# Adafruit_DotStar_2020_8x8_Matrix.net
KiCad netlist of a schematic drawn in EAGLE
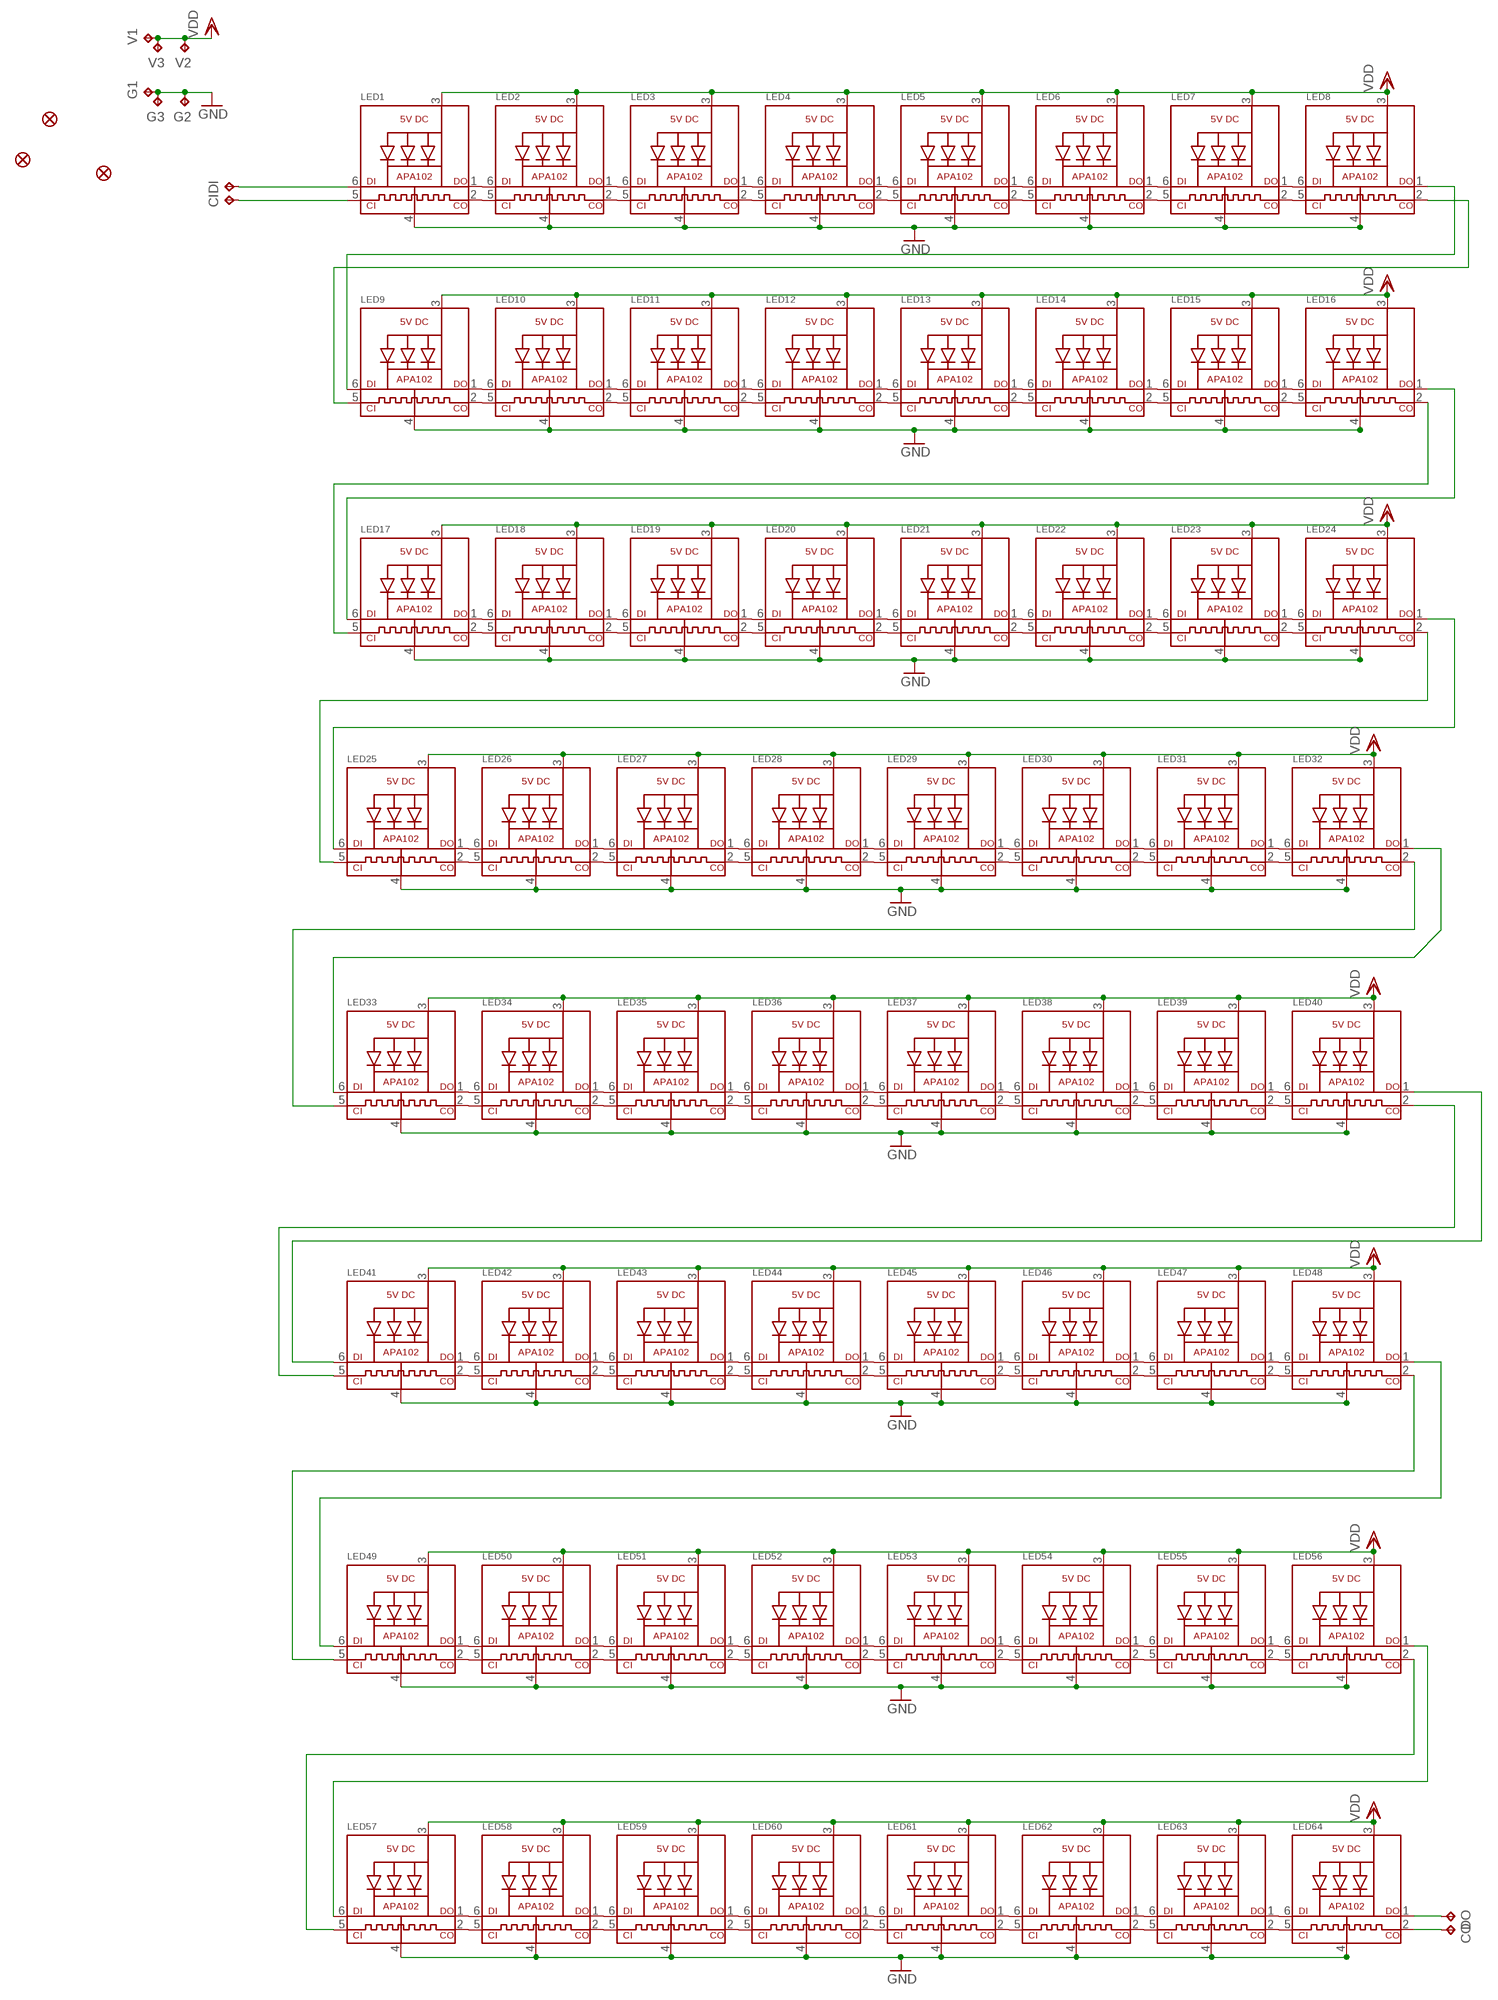
[diagram p0: schematic, sheet 1]

(export (version "E")
  (design (tool "Eeschema 10.0.6"))
  (components
    (comp (ref "CI")
      (value "TPTP20R")
      (footprint "eagle-import:TP20R")
      (libsource (lib "eagle-import") (part "TPTP20R"))
    )
    (comp (ref "CO")
      (value "TPTP20R")
      (footprint "eagle-import:TP20R")
      (libsource (lib "eagle-import") (part "TPTP20R"))
    )
    (comp (ref "DI")
      (value "TPTP20R")
      (footprint "eagle-import:TP20R")
      (libsource (lib "eagle-import") (part "TPTP20R"))
    )
    (comp (ref "DO")
      (value "TPTP20R")
      (footprint "eagle-import:TP20R")
      (libsource (lib "eagle-import") (part "TPTP20R"))
    )
    (comp (ref "FID1")
      (value "FIDUCIAL_0.5MM")
      (footprint "eagle-import:FIDUCIAL_0.5MM")
      (libsource (lib "eagle-import") (part "FIDUCIAL_0.5MM"))
    )
    (comp (ref "FID2")
      (value "FIDUCIAL_0.5MM")
      (footprint "eagle-import:FIDUCIAL_0.5MM")
      (libsource (lib "eagle-import") (part "FIDUCIAL_0.5MM"))
    )
    (comp (ref "FID3")
      (value "FIDUCIAL_0.5MM")
      (footprint "eagle-import:FIDUCIAL_0.5MM")
      (libsource (lib "eagle-import") (part "FIDUCIAL_0.5MM"))
    )
    (comp (ref "G1")
      (value "TPTP20R")
      (footprint "eagle-import:TP20R")
      (libsource (lib "eagle-import") (part "TPTP20R"))
    )
    (comp (ref "G2")
      (value "TPTP20R")
      (footprint "eagle-import:TP20R")
      (libsource (lib "eagle-import") (part "TPTP20R"))
    )
    (comp (ref "G3")
      (value "TPTP20R")
      (footprint "eagle-import:TP20R")
      (libsource (lib "eagle-import") (part "TPTP20R"))
    )
    (comp (ref "LED1")
      (value "APA1022020")
      (footprint "eagle-import:APA102_2020")
      (libsource (lib "eagle-import") (part "APA1022020"))
    )
    (comp (ref "LED2")
      (value "APA1022020")
      (footprint "eagle-import:APA102_2020")
      (libsource (lib "eagle-import") (part "APA1022020"))
    )
    (comp (ref "LED3")
      (value "APA1022020")
      (footprint "eagle-import:APA102_2020")
      (libsource (lib "eagle-import") (part "APA1022020"))
    )
    (comp (ref "LED4")
      (value "APA1022020")
      (footprint "eagle-import:APA102_2020")
      (libsource (lib "eagle-import") (part "APA1022020"))
    )
    (comp (ref "LED5")
      (value "APA1022020")
      (footprint "eagle-import:APA102_2020")
      (libsource (lib "eagle-import") (part "APA1022020"))
    )
    (comp (ref "LED6")
      (value "APA1022020")
      (footprint "eagle-import:APA102_2020")
      (libsource (lib "eagle-import") (part "APA1022020"))
    )
    (comp (ref "LED7")
      (value "APA1022020")
      (footprint "eagle-import:APA102_2020")
      (libsource (lib "eagle-import") (part "APA1022020"))
    )
    (comp (ref "LED8")
      (value "APA1022020")
      (footprint "eagle-import:APA102_2020")
      (libsource (lib "eagle-import") (part "APA1022020"))
    )
    (comp (ref "LED9")
      (value "APA1022020")
      (footprint "eagle-import:APA102_2020")
      (libsource (lib "eagle-import") (part "APA1022020"))
    )
    (comp (ref "LED10")
      (value "APA1022020")
      (footprint "eagle-import:APA102_2020")
      (libsource (lib "eagle-import") (part "APA1022020"))
    )
    (comp (ref "LED11")
      (value "APA1022020")
      (footprint "eagle-import:APA102_2020")
      (libsource (lib "eagle-import") (part "APA1022020"))
    )
    (comp (ref "LED12")
      (value "APA1022020")
      (footprint "eagle-import:APA102_2020")
      (libsource (lib "eagle-import") (part "APA1022020"))
    )
    (comp (ref "LED13")
      (value "APA1022020")
      (footprint "eagle-import:APA102_2020")
      (libsource (lib "eagle-import") (part "APA1022020"))
    )
    (comp (ref "LED14")
      (value "APA1022020")
      (footprint "eagle-import:APA102_2020")
      (libsource (lib "eagle-import") (part "APA1022020"))
    )
    (comp (ref "LED15")
      (value "APA1022020")
      (footprint "eagle-import:APA102_2020")
      (libsource (lib "eagle-import") (part "APA1022020"))
    )
    (comp (ref "LED16")
      (value "APA1022020")
      (footprint "eagle-import:APA102_2020")
      (libsource (lib "eagle-import") (part "APA1022020"))
    )
    (comp (ref "LED17")
      (value "APA1022020")
      (footprint "eagle-import:APA102_2020")
      (libsource (lib "eagle-import") (part "APA1022020"))
    )
    (comp (ref "LED18")
      (value "APA1022020")
      (footprint "eagle-import:APA102_2020")
      (libsource (lib "eagle-import") (part "APA1022020"))
    )
    (comp (ref "LED19")
      (value "APA1022020")
      (footprint "eagle-import:APA102_2020")
      (libsource (lib "eagle-import") (part "APA1022020"))
    )
    (comp (ref "LED20")
      (value "APA1022020")
      (footprint "eagle-import:APA102_2020")
      (libsource (lib "eagle-import") (part "APA1022020"))
    )
    (comp (ref "LED21")
      (value "APA1022020")
      (footprint "eagle-import:APA102_2020")
      (libsource (lib "eagle-import") (part "APA1022020"))
    )
    (comp (ref "LED22")
      (value "APA1022020")
      (footprint "eagle-import:APA102_2020")
      (libsource (lib "eagle-import") (part "APA1022020"))
    )
    (comp (ref "LED23")
      (value "APA1022020")
      (footprint "eagle-import:APA102_2020")
      (libsource (lib "eagle-import") (part "APA1022020"))
    )
    (comp (ref "LED24")
      (value "APA1022020")
      (footprint "eagle-import:APA102_2020")
      (libsource (lib "eagle-import") (part "APA1022020"))
    )
    (comp (ref "LED25")
      (value "APA1022020")
      (footprint "eagle-import:APA102_2020")
      (libsource (lib "eagle-import") (part "APA1022020"))
    )
    (comp (ref "LED26")
      (value "APA1022020")
      (footprint "eagle-import:APA102_2020")
      (libsource (lib "eagle-import") (part "APA1022020"))
    )
    (comp (ref "LED27")
      (value "APA1022020")
      (footprint "eagle-import:APA102_2020")
      (libsource (lib "eagle-import") (part "APA1022020"))
    )
    (comp (ref "LED28")
      (value "APA1022020")
      (footprint "eagle-import:APA102_2020")
      (libsource (lib "eagle-import") (part "APA1022020"))
    )
    (comp (ref "LED29")
      (value "APA1022020")
      (footprint "eagle-import:APA102_2020")
      (libsource (lib "eagle-import") (part "APA1022020"))
    )
    (comp (ref "LED30")
      (value "APA1022020")
      (footprint "eagle-import:APA102_2020")
      (libsource (lib "eagle-import") (part "APA1022020"))
    )
    (comp (ref "LED31")
      (value "APA1022020")
      (footprint "eagle-import:APA102_2020")
      (libsource (lib "eagle-import") (part "APA1022020"))
    )
    (comp (ref "LED32")
      (value "APA1022020")
      (footprint "eagle-import:APA102_2020")
      (libsource (lib "eagle-import") (part "APA1022020"))
    )
    (comp (ref "LED33")
      (value "APA1022020")
      (footprint "eagle-import:APA102_2020")
      (libsource (lib "eagle-import") (part "APA1022020"))
    )
    (comp (ref "LED34")
      (value "APA1022020")
      (footprint "eagle-import:APA102_2020")
      (libsource (lib "eagle-import") (part "APA1022020"))
    )
    (comp (ref "LED35")
      (value "APA1022020")
      (footprint "eagle-import:APA102_2020")
      (libsource (lib "eagle-import") (part "APA1022020"))
    )
    (comp (ref "LED36")
      (value "APA1022020")
      (footprint "eagle-import:APA102_2020")
      (libsource (lib "eagle-import") (part "APA1022020"))
    )
    (comp (ref "LED37")
      (value "APA1022020")
      (footprint "eagle-import:APA102_2020")
      (libsource (lib "eagle-import") (part "APA1022020"))
    )
    (comp (ref "LED38")
      (value "APA1022020")
      (footprint "eagle-import:APA102_2020")
      (libsource (lib "eagle-import") (part "APA1022020"))
    )
    (comp (ref "LED39")
      (value "APA1022020")
      (footprint "eagle-import:APA102_2020")
      (libsource (lib "eagle-import") (part "APA1022020"))
    )
    (comp (ref "LED40")
      (value "APA1022020")
      (footprint "eagle-import:APA102_2020")
      (libsource (lib "eagle-import") (part "APA1022020"))
    )
    (comp (ref "LED41")
      (value "APA1022020")
      (footprint "eagle-import:APA102_2020")
      (libsource (lib "eagle-import") (part "APA1022020"))
    )
    (comp (ref "LED42")
      (value "APA1022020")
      (footprint "eagle-import:APA102_2020")
      (libsource (lib "eagle-import") (part "APA1022020"))
    )
    (comp (ref "LED43")
      (value "APA1022020")
      (footprint "eagle-import:APA102_2020")
      (libsource (lib "eagle-import") (part "APA1022020"))
    )
    (comp (ref "LED44")
      (value "APA1022020")
      (footprint "eagle-import:APA102_2020")
      (libsource (lib "eagle-import") (part "APA1022020"))
    )
    (comp (ref "LED45")
      (value "APA1022020")
      (footprint "eagle-import:APA102_2020")
      (libsource (lib "eagle-import") (part "APA1022020"))
    )
    (comp (ref "LED46")
      (value "APA1022020")
      (footprint "eagle-import:APA102_2020")
      (libsource (lib "eagle-import") (part "APA1022020"))
    )
    (comp (ref "LED47")
      (value "APA1022020")
      (footprint "eagle-import:APA102_2020")
      (libsource (lib "eagle-import") (part "APA1022020"))
    )
    (comp (ref "LED48")
      (value "APA1022020")
      (footprint "eagle-import:APA102_2020")
      (libsource (lib "eagle-import") (part "APA1022020"))
    )
    (comp (ref "LED49")
      (value "APA1022020")
      (footprint "eagle-import:APA102_2020")
      (libsource (lib "eagle-import") (part "APA1022020"))
    )
    (comp (ref "LED50")
      (value "APA1022020")
      (footprint "eagle-import:APA102_2020")
      (libsource (lib "eagle-import") (part "APA1022020"))
    )
    (comp (ref "LED51")
      (value "APA1022020")
      (footprint "eagle-import:APA102_2020")
      (libsource (lib "eagle-import") (part "APA1022020"))
    )
    (comp (ref "LED52")
      (value "APA1022020")
      (footprint "eagle-import:APA102_2020")
      (libsource (lib "eagle-import") (part "APA1022020"))
    )
    (comp (ref "LED53")
      (value "APA1022020")
      (footprint "eagle-import:APA102_2020")
      (libsource (lib "eagle-import") (part "APA1022020"))
    )
    (comp (ref "LED54")
      (value "APA1022020")
      (footprint "eagle-import:APA102_2020")
      (libsource (lib "eagle-import") (part "APA1022020"))
    )
    (comp (ref "LED55")
      (value "APA1022020")
      (footprint "eagle-import:APA102_2020")
      (libsource (lib "eagle-import") (part "APA1022020"))
    )
    (comp (ref "LED56")
      (value "APA1022020")
      (footprint "eagle-import:APA102_2020")
      (libsource (lib "eagle-import") (part "APA1022020"))
    )
    (comp (ref "LED57")
      (value "APA1022020")
      (footprint "eagle-import:APA102_2020")
      (libsource (lib "eagle-import") (part "APA1022020"))
    )
    (comp (ref "LED58")
      (value "APA1022020")
      (footprint "eagle-import:APA102_2020")
      (libsource (lib "eagle-import") (part "APA1022020"))
    )
    (comp (ref "LED59")
      (value "APA1022020")
      (footprint "eagle-import:APA102_2020")
      (libsource (lib "eagle-import") (part "APA1022020"))
    )
    (comp (ref "LED60")
      (value "APA1022020")
      (footprint "eagle-import:APA102_2020")
      (libsource (lib "eagle-import") (part "APA1022020"))
    )
    (comp (ref "LED61")
      (value "APA1022020")
      (footprint "eagle-import:APA102_2020")
      (libsource (lib "eagle-import") (part "APA1022020"))
    )
    (comp (ref "LED62")
      (value "APA1022020")
      (footprint "eagle-import:APA102_2020")
      (libsource (lib "eagle-import") (part "APA1022020"))
    )
    (comp (ref "LED63")
      (value "APA1022020")
      (footprint "eagle-import:APA102_2020")
      (libsource (lib "eagle-import") (part "APA1022020"))
    )
    (comp (ref "LED64")
      (value "APA1022020")
      (footprint "eagle-import:APA102_2020")
      (libsource (lib "eagle-import") (part "APA1022020"))
    )
    (comp (ref "V1")
      (value "TPTP20R")
      (footprint "eagle-import:TP20R")
      (libsource (lib "eagle-import") (part "TPTP20R"))
    )
    (comp (ref "V2")
      (value "TPTP20R")
      (footprint "eagle-import:TP20R")
      (libsource (lib "eagle-import") (part "TPTP20R"))
    )
    (comp (ref "V3")
      (value "TPTP20R")
      (footprint "eagle-import:TP20R")
      (libsource (lib "eagle-import") (part "TPTP20R"))
    )
  )
  (nets
    (net (code "1") (name "GND") (class "Default")
      (node (ref "G1") (pin "TP") (pinfunction "TP_TP") (pintype "input"))
      (node (ref "G2") (pin "TP") (pinfunction "TP_TP") (pintype "input"))
      (node (ref "G3") (pin "TP") (pinfunction "TP_TP") (pintype "input"))
      (node (ref "LED1") (pin "4") (pinfunction "GND_4") (pintype "power_in"))
      (node (ref "LED10") (pin "4") (pinfunction "GND_4") (pintype "power_in"))
      (node (ref "LED11") (pin "4") (pinfunction "GND_4") (pintype "power_in"))
      (node (ref "LED12") (pin "4") (pinfunction "GND_4") (pintype "power_in"))
      (node (ref "LED13") (pin "4") (pinfunction "GND_4") (pintype "power_in"))
      (node (ref "LED14") (pin "4") (pinfunction "GND_4") (pintype "power_in"))
      (node (ref "LED15") (pin "4") (pinfunction "GND_4") (pintype "power_in"))
      (node (ref "LED16") (pin "4") (pinfunction "GND_4") (pintype "power_in"))
      (node (ref "LED17") (pin "4") (pinfunction "GND_4") (pintype "power_in"))
      (node (ref "LED18") (pin "4") (pinfunction "GND_4") (pintype "power_in"))
      (node (ref "LED19") (pin "4") (pinfunction "GND_4") (pintype "power_in"))
      (node (ref "LED2") (pin "4") (pinfunction "GND_4") (pintype "power_in"))
      (node (ref "LED20") (pin "4") (pinfunction "GND_4") (pintype "power_in"))
      (node (ref "LED21") (pin "4") (pinfunction "GND_4") (pintype "power_in"))
      (node (ref "LED22") (pin "4") (pinfunction "GND_4") (pintype "power_in"))
      (node (ref "LED23") (pin "4") (pinfunction "GND_4") (pintype "power_in"))
      (node (ref "LED24") (pin "4") (pinfunction "GND_4") (pintype "power_in"))
      (node (ref "LED25") (pin "4") (pinfunction "GND_4") (pintype "power_in"))
      (node (ref "LED26") (pin "4") (pinfunction "GND_4") (pintype "power_in"))
      (node (ref "LED27") (pin "4") (pinfunction "GND_4") (pintype "power_in"))
      (node (ref "LED28") (pin "4") (pinfunction "GND_4") (pintype "power_in"))
      (node (ref "LED29") (pin "4") (pinfunction "GND_4") (pintype "power_in"))
      (node (ref "LED3") (pin "4") (pinfunction "GND_4") (pintype "power_in"))
      (node (ref "LED30") (pin "4") (pinfunction "GND_4") (pintype "power_in"))
      (node (ref "LED31") (pin "4") (pinfunction "GND_4") (pintype "power_in"))
      (node (ref "LED32") (pin "4") (pinfunction "GND_4") (pintype "power_in"))
      (node (ref "LED33") (pin "4") (pinfunction "GND_4") (pintype "power_in"))
      (node (ref "LED34") (pin "4") (pinfunction "GND_4") (pintype "power_in"))
      (node (ref "LED35") (pin "4") (pinfunction "GND_4") (pintype "power_in"))
      (node (ref "LED36") (pin "4") (pinfunction "GND_4") (pintype "power_in"))
      (node (ref "LED37") (pin "4") (pinfunction "GND_4") (pintype "power_in"))
      (node (ref "LED38") (pin "4") (pinfunction "GND_4") (pintype "power_in"))
      (node (ref "LED39") (pin "4") (pinfunction "GND_4") (pintype "power_in"))
      (node (ref "LED4") (pin "4") (pinfunction "GND_4") (pintype "power_in"))
      (node (ref "LED40") (pin "4") (pinfunction "GND_4") (pintype "power_in"))
      (node (ref "LED41") (pin "4") (pinfunction "GND_4") (pintype "power_in"))
      (node (ref "LED42") (pin "4") (pinfunction "GND_4") (pintype "power_in"))
      (node (ref "LED43") (pin "4") (pinfunction "GND_4") (pintype "power_in"))
      (node (ref "LED44") (pin "4") (pinfunction "GND_4") (pintype "power_in"))
      (node (ref "LED45") (pin "4") (pinfunction "GND_4") (pintype "power_in"))
      (node (ref "LED46") (pin "4") (pinfunction "GND_4") (pintype "power_in"))
      (node (ref "LED47") (pin "4") (pinfunction "GND_4") (pintype "power_in"))
      (node (ref "LED48") (pin "4") (pinfunction "GND_4") (pintype "power_in"))
      (node (ref "LED49") (pin "4") (pinfunction "GND_4") (pintype "power_in"))
      (node (ref "LED5") (pin "4") (pinfunction "GND_4") (pintype "power_in"))
      (node (ref "LED50") (pin "4") (pinfunction "GND_4") (pintype "power_in"))
      (node (ref "LED51") (pin "4") (pinfunction "GND_4") (pintype "power_in"))
      (node (ref "LED52") (pin "4") (pinfunction "GND_4") (pintype "power_in"))
      (node (ref "LED53") (pin "4") (pinfunction "GND_4") (pintype "power_in"))
      (node (ref "LED54") (pin "4") (pinfunction "GND_4") (pintype "power_in"))
      (node (ref "LED55") (pin "4") (pinfunction "GND_4") (pintype "power_in"))
      (node (ref "LED56") (pin "4") (pinfunction "GND_4") (pintype "power_in"))
      (node (ref "LED57") (pin "4") (pinfunction "GND_4") (pintype "power_in"))
      (node (ref "LED58") (pin "4") (pinfunction "GND_4") (pintype "power_in"))
      (node (ref "LED59") (pin "4") (pinfunction "GND_4") (pintype "power_in"))
      (node (ref "LED6") (pin "4") (pinfunction "GND_4") (pintype "power_in"))
      (node (ref "LED60") (pin "4") (pinfunction "GND_4") (pintype "power_in"))
      (node (ref "LED61") (pin "4") (pinfunction "GND_4") (pintype "power_in"))
      (node (ref "LED62") (pin "4") (pinfunction "GND_4") (pintype "power_in"))
      (node (ref "LED63") (pin "4") (pinfunction "GND_4") (pintype "power_in"))
      (node (ref "LED64") (pin "4") (pinfunction "GND_4") (pintype "power_in"))
      (node (ref "LED7") (pin "4") (pinfunction "GND_4") (pintype "power_in"))
      (node (ref "LED8") (pin "4") (pinfunction "GND_4") (pintype "power_in"))
      (node (ref "LED9") (pin "4") (pinfunction "GND_4") (pintype "power_in"))
    )
    (net (code "2") (name "Net-(LED1-CKI)") (class "Default")
      (node (ref "CI") (pin "TP") (pinfunction "TP_TP") (pintype "input"))
      (node (ref "LED1") (pin "5") (pinfunction "CKI_5") (pintype "input"))
    )
    (net (code "3") (name "Net-(LED1-CKO)") (class "Default")
      (node (ref "LED1") (pin "2") (pinfunction "CKO_2") (pintype "output"))
      (node (ref "LED2") (pin "5") (pinfunction "CKI_5") (pintype "input"))
    )
    (net (code "4") (name "Net-(LED1-DI)") (class "Default")
      (node (ref "DI") (pin "TP") (pinfunction "TP_TP") (pintype "input"))
      (node (ref "LED1") (pin "6") (pinfunction "DI_6") (pintype "input"))
    )
    (net (code "5") (name "Net-(LED1-DO)") (class "Default")
      (node (ref "LED1") (pin "1") (pinfunction "DO_1") (pintype "output"))
      (node (ref "LED2") (pin "6") (pinfunction "DI_6") (pintype "input"))
    )
    (net (code "6") (name "Net-(LED2-CKO)") (class "Default")
      (node (ref "LED2") (pin "2") (pinfunction "CKO_2") (pintype "output"))
      (node (ref "LED3") (pin "5") (pinfunction "CKI_5") (pintype "input"))
    )
    (net (code "7") (name "Net-(LED2-DO)") (class "Default")
      (node (ref "LED2") (pin "1") (pinfunction "DO_1") (pintype "output"))
      (node (ref "LED3") (pin "6") (pinfunction "DI_6") (pintype "input"))
    )
    (net (code "8") (name "Net-(LED3-CKO)") (class "Default")
      (node (ref "LED3") (pin "2") (pinfunction "CKO_2") (pintype "output"))
      (node (ref "LED4") (pin "5") (pinfunction "CKI_5") (pintype "input"))
    )
    (net (code "9") (name "Net-(LED3-DO)") (class "Default")
      (node (ref "LED3") (pin "1") (pinfunction "DO_1") (pintype "output"))
      (node (ref "LED4") (pin "6") (pinfunction "DI_6") (pintype "input"))
    )
    (net (code "10") (name "Net-(LED4-CKO)") (class "Default")
      (node (ref "LED4") (pin "2") (pinfunction "CKO_2") (pintype "output"))
      (node (ref "LED5") (pin "5") (pinfunction "CKI_5") (pintype "input"))
    )
    (net (code "11") (name "Net-(LED4-DO)") (class "Default")
      (node (ref "LED4") (pin "1") (pinfunction "DO_1") (pintype "output"))
      (node (ref "LED5") (pin "6") (pinfunction "DI_6") (pintype "input"))
    )
    (net (code "12") (name "Net-(LED5-CKO)") (class "Default")
      (node (ref "LED5") (pin "2") (pinfunction "CKO_2") (pintype "output"))
      (node (ref "LED6") (pin "5") (pinfunction "CKI_5") (pintype "input"))
    )
    (net (code "13") (name "Net-(LED5-DO)") (class "Default")
      (node (ref "LED5") (pin "1") (pinfunction "DO_1") (pintype "output"))
      (node (ref "LED6") (pin "6") (pinfunction "DI_6") (pintype "input"))
    )
    (net (code "14") (name "Net-(LED6-CKO)") (class "Default")
      (node (ref "LED6") (pin "2") (pinfunction "CKO_2") (pintype "output"))
      (node (ref "LED7") (pin "5") (pinfunction "CKI_5") (pintype "input"))
    )
    (net (code "15") (name "Net-(LED6-DO)") (class "Default")
      (node (ref "LED6") (pin "1") (pinfunction "DO_1") (pintype "output"))
      (node (ref "LED7") (pin "6") (pinfunction "DI_6") (pintype "input"))
    )
    (net (code "16") (name "Net-(LED7-CKO)") (class "Default")
      (node (ref "LED7") (pin "2") (pinfunction "CKO_2") (pintype "output"))
      (node (ref "LED8") (pin "5") (pinfunction "CKI_5") (pintype "input"))
    )
    (net (code "17") (name "Net-(LED7-DO)") (class "Default")
      (node (ref "LED7") (pin "1") (pinfunction "DO_1") (pintype "output"))
      (node (ref "LED8") (pin "6") (pinfunction "DI_6") (pintype "input"))
    )
    (net (code "18") (name "Net-(LED8-CKO)") (class "Default")
      (node (ref "LED8") (pin "2") (pinfunction "CKO_2") (pintype "output"))
      (node (ref "LED9") (pin "5") (pinfunction "CKI_5") (pintype "input"))
    )
    (net (code "19") (name "Net-(LED8-DO)") (class "Default")
      (node (ref "LED8") (pin "1") (pinfunction "DO_1") (pintype "output"))
      (node (ref "LED9") (pin "6") (pinfunction "DI_6") (pintype "input"))
    )
    (net (code "20") (name "Net-(LED10-CKI)") (class "Default")
      (node (ref "LED10") (pin "5") (pinfunction "CKI_5") (pintype "input"))
      (node (ref "LED9") (pin "2") (pinfunction "CKO_2") (pintype "output"))
    )
    (net (code "21") (name "Net-(LED10-CKO)") (class "Default")
      (node (ref "LED10") (pin "2") (pinfunction "CKO_2") (pintype "output"))
      (node (ref "LED11") (pin "5") (pinfunction "CKI_5") (pintype "input"))
    )
    (net (code "22") (name "Net-(LED10-DI)") (class "Default")
      (node (ref "LED10") (pin "6") (pinfunction "DI_6") (pintype "input"))
      (node (ref "LED9") (pin "1") (pinfunction "DO_1") (pintype "output"))
    )
    (net (code "23") (name "Net-(LED10-DO)") (class "Default")
      (node (ref "LED10") (pin "1") (pinfunction "DO_1") (pintype "output"))
      (node (ref "LED11") (pin "6") (pinfunction "DI_6") (pintype "input"))
    )
    (net (code "24") (name "Net-(LED11-CKO)") (class "Default")
      (node (ref "LED11") (pin "2") (pinfunction "CKO_2") (pintype "output"))
      (node (ref "LED12") (pin "5") (pinfunction "CKI_5") (pintype "input"))
    )
    (net (code "25") (name "Net-(LED11-DO)") (class "Default")
      (node (ref "LED11") (pin "1") (pinfunction "DO_1") (pintype "output"))
      (node (ref "LED12") (pin "6") (pinfunction "DI_6") (pintype "input"))
    )
    (net (code "26") (name "Net-(LED12-CKO)") (class "Default")
      (node (ref "LED12") (pin "2") (pinfunction "CKO_2") (pintype "output"))
      (node (ref "LED13") (pin "5") (pinfunction "CKI_5") (pintype "input"))
    )
    (net (code "27") (name "Net-(LED12-DO)") (class "Default")
      (node (ref "LED12") (pin "1") (pinfunction "DO_1") (pintype "output"))
      (node (ref "LED13") (pin "6") (pinfunction "DI_6") (pintype "input"))
    )
    (net (code "28") (name "Net-(LED13-CKO)") (class "Default")
      (node (ref "LED13") (pin "2") (pinfunction "CKO_2") (pintype "output"))
      (node (ref "LED14") (pin "5") (pinfunction "CKI_5") (pintype "input"))
    )
    (net (code "29") (name "Net-(LED13-DO)") (class "Default")
      (node (ref "LED13") (pin "1") (pinfunction "DO_1") (pintype "output"))
      (node (ref "LED14") (pin "6") (pinfunction "DI_6") (pintype "input"))
    )
    (net (code "30") (name "Net-(LED14-CKO)") (class "Default")
      (node (ref "LED14") (pin "2") (pinfunction "CKO_2") (pintype "output"))
      (node (ref "LED15") (pin "5") (pinfunction "CKI_5") (pintype "input"))
    )
    (net (code "31") (name "Net-(LED14-DO)") (class "Default")
      (node (ref "LED14") (pin "1") (pinfunction "DO_1") (pintype "output"))
      (node (ref "LED15") (pin "6") (pinfunction "DI_6") (pintype "input"))
    )
    (net (code "32") (name "Net-(LED15-CKO)") (class "Default")
      (node (ref "LED15") (pin "2") (pinfunction "CKO_2") (pintype "output"))
      (node (ref "LED16") (pin "5") (pinfunction "CKI_5") (pintype "input"))
    )
    (net (code "33") (name "Net-(LED15-DO)") (class "Default")
      (node (ref "LED15") (pin "1") (pinfunction "DO_1") (pintype "output"))
      (node (ref "LED16") (pin "6") (pinfunction "DI_6") (pintype "input"))
    )
    (net (code "34") (name "Net-(LED16-CKO)") (class "Default")
      (node (ref "LED16") (pin "2") (pinfunction "CKO_2") (pintype "output"))
      (node (ref "LED17") (pin "5") (pinfunction "CKI_5") (pintype "input"))
    )
    (net (code "35") (name "Net-(LED16-DO)") (class "Default")
      (node (ref "LED16") (pin "1") (pinfunction "DO_1") (pintype "output"))
      (node (ref "LED17") (pin "6") (pinfunction "DI_6") (pintype "input"))
    )
    (net (code "36") (name "Net-(LED17-CKO)") (class "Default")
      (node (ref "LED17") (pin "2") (pinfunction "CKO_2") (pintype "output"))
      (node (ref "LED18") (pin "5") (pinfunction "CKI_5") (pintype "input"))
    )
    (net (code "37") (name "Net-(LED17-DO)") (class "Default")
      (node (ref "LED17") (pin "1") (pinfunction "DO_1") (pintype "output"))
      (node (ref "LED18") (pin "6") (pinfunction "DI_6") (pintype "input"))
    )
    (net (code "38") (name "Net-(LED18-CKO)") (class "Default")
      (node (ref "LED18") (pin "2") (pinfunction "CKO_2") (pintype "output"))
      (node (ref "LED19") (pin "5") (pinfunction "CKI_5") (pintype "input"))
    )
    (net (code "39") (name "Net-(LED18-DO)") (class "Default")
      (node (ref "LED18") (pin "1") (pinfunction "DO_1") (pintype "output"))
      (node (ref "LED19") (pin "6") (pinfunction "DI_6") (pintype "input"))
    )
    (net (code "40") (name "Net-(LED19-CKO)") (class "Default")
      (node (ref "LED19") (pin "2") (pinfunction "CKO_2") (pintype "output"))
      (node (ref "LED20") (pin "5") (pinfunction "CKI_5") (pintype "input"))
    )
    (net (code "41") (name "Net-(LED19-DO)") (class "Default")
      (node (ref "LED19") (pin "1") (pinfunction "DO_1") (pintype "output"))
      (node (ref "LED20") (pin "6") (pinfunction "DI_6") (pintype "input"))
    )
    (net (code "42") (name "Net-(LED20-CKO)") (class "Default")
      (node (ref "LED20") (pin "2") (pinfunction "CKO_2") (pintype "output"))
      (node (ref "LED21") (pin "5") (pinfunction "CKI_5") (pintype "input"))
    )
    (net (code "43") (name "Net-(LED20-DO)") (class "Default")
      (node (ref "LED20") (pin "1") (pinfunction "DO_1") (pintype "output"))
      (node (ref "LED21") (pin "6") (pinfunction "DI_6") (pintype "input"))
    )
    (net (code "44") (name "Net-(LED21-CKO)") (class "Default")
      (node (ref "LED21") (pin "2") (pinfunction "CKO_2") (pintype "output"))
      (node (ref "LED22") (pin "5") (pinfunction "CKI_5") (pintype "input"))
    )
    (net (code "45") (name "Net-(LED21-DO)") (class "Default")
      (node (ref "LED21") (pin "1") (pinfunction "DO_1") (pintype "output"))
      (node (ref "LED22") (pin "6") (pinfunction "DI_6") (pintype "input"))
    )
    (net (code "46") (name "Net-(LED22-CKO)") (class "Default")
      (node (ref "LED22") (pin "2") (pinfunction "CKO_2") (pintype "output"))
      (node (ref "LED23") (pin "5") (pinfunction "CKI_5") (pintype "input"))
    )
    (net (code "47") (name "Net-(LED22-DO)") (class "Default")
      (node (ref "LED22") (pin "1") (pinfunction "DO_1") (pintype "output"))
      (node (ref "LED23") (pin "6") (pinfunction "DI_6") (pintype "input"))
    )
    (net (code "48") (name "Net-(LED23-CKO)") (class "Default")
      (node (ref "LED23") (pin "2") (pinfunction "CKO_2") (pintype "output"))
      (node (ref "LED24") (pin "5") (pinfunction "CKI_5") (pintype "input"))
    )
    (net (code "49") (name "Net-(LED23-DO)") (class "Default")
      (node (ref "LED23") (pin "1") (pinfunction "DO_1") (pintype "output"))
      (node (ref "LED24") (pin "6") (pinfunction "DI_6") (pintype "input"))
    )
    (net (code "50") (name "Net-(LED24-CKO)") (class "Default")
      (node (ref "LED24") (pin "2") (pinfunction "CKO_2") (pintype "output"))
      (node (ref "LED25") (pin "5") (pinfunction "CKI_5") (pintype "input"))
    )
    (net (code "51") (name "Net-(LED24-DO)") (class "Default")
      (node (ref "LED24") (pin "1") (pinfunction "DO_1") (pintype "output"))
      (node (ref "LED25") (pin "6") (pinfunction "DI_6") (pintype "input"))
    )
    (net (code "52") (name "Net-(LED25-CKO)") (class "Default")
      (node (ref "LED25") (pin "2") (pinfunction "CKO_2") (pintype "output"))
      (node (ref "LED26") (pin "5") (pinfunction "CKI_5") (pintype "input"))
    )
    (net (code "53") (name "Net-(LED25-DO)") (class "Default")
      (node (ref "LED25") (pin "1") (pinfunction "DO_1") (pintype "output"))
      (node (ref "LED26") (pin "6") (pinfunction "DI_6") (pintype "input"))
    )
    (net (code "54") (name "Net-(LED26-CKO)") (class "Default")
      (node (ref "LED26") (pin "2") (pinfunction "CKO_2") (pintype "output"))
      (node (ref "LED27") (pin "5") (pinfunction "CKI_5") (pintype "input"))
    )
    (net (code "55") (name "Net-(LED26-DO)") (class "Default")
      (node (ref "LED26") (pin "1") (pinfunction "DO_1") (pintype "output"))
      (node (ref "LED27") (pin "6") (pinfunction "DI_6") (pintype "input"))
    )
    (net (code "56") (name "Net-(LED27-CKO)") (class "Default")
      (node (ref "LED27") (pin "2") (pinfunction "CKO_2") (pintype "output"))
      (node (ref "LED28") (pin "5") (pinfunction "CKI_5") (pintype "input"))
    )
    (net (code "57") (name "Net-(LED27-DO)") (class "Default")
      (node (ref "LED27") (pin "1") (pinfunction "DO_1") (pintype "output"))
      (node (ref "LED28") (pin "6") (pinfunction "DI_6") (pintype "input"))
    )
    (net (code "58") (name "Net-(LED28-CKO)") (class "Default")
      (node (ref "LED28") (pin "2") (pinfunction "CKO_2") (pintype "output"))
      (node (ref "LED29") (pin "5") (pinfunction "CKI_5") (pintype "input"))
    )
    (net (code "59") (name "Net-(LED28-DO)") (class "Default")
      (node (ref "LED28") (pin "1") (pinfunction "DO_1") (pintype "output"))
      (node (ref "LED29") (pin "6") (pinfunction "DI_6") (pintype "input"))
    )
    (net (code "60") (name "Net-(LED29-CKO)") (class "Default")
      (node (ref "LED29") (pin "2") (pinfunction "CKO_2") (pintype "output"))
      (node (ref "LED30") (pin "5") (pinfunction "CKI_5") (pintype "input"))
    )
    (net (code "61") (name "Net-(LED29-DO)") (class "Default")
      (node (ref "LED29") (pin "1") (pinfunction "DO_1") (pintype "output"))
      (node (ref "LED30") (pin "6") (pinfunction "DI_6") (pintype "input"))
    )
    (net (code "62") (name "Net-(LED30-CKO)") (class "Default")
      (node (ref "LED30") (pin "2") (pinfunction "CKO_2") (pintype "output"))
      (node (ref "LED31") (pin "5") (pinfunction "CKI_5") (pintype "input"))
    )
    (net (code "63") (name "Net-(LED30-DO)") (class "Default")
      (node (ref "LED30") (pin "1") (pinfunction "DO_1") (pintype "output"))
      (node (ref "LED31") (pin "6") (pinfunction "DI_6") (pintype "input"))
    )
    (net (code "64") (name "Net-(LED31-CKO)") (class "Default")
      (node (ref "LED31") (pin "2") (pinfunction "CKO_2") (pintype "output"))
      (node (ref "LED32") (pin "5") (pinfunction "CKI_5") (pintype "input"))
    )
    (net (code "65") (name "Net-(LED31-DO)") (class "Default")
      (node (ref "LED31") (pin "1") (pinfunction "DO_1") (pintype "output"))
      (node (ref "LED32") (pin "6") (pinfunction "DI_6") (pintype "input"))
    )
    (net (code "66") (name "Net-(LED32-CKO)") (class "Default")
      (node (ref "LED32") (pin "2") (pinfunction "CKO_2") (pintype "output"))
      (node (ref "LED33") (pin "5") (pinfunction "CKI_5") (pintype "input"))
    )
    (net (code "67") (name "Net-(LED32-DO)") (class "Default")
      (node (ref "LED32") (pin "1") (pinfunction "DO_1") (pintype "output"))
      (node (ref "LED33") (pin "6") (pinfunction "DI_6") (pintype "input"))
    )
    (net (code "68") (name "Net-(LED33-CKO)") (class "Default")
      (node (ref "LED33") (pin "2") (pinfunction "CKO_2") (pintype "output"))
      (node (ref "LED34") (pin "5") (pinfunction "CKI_5") (pintype "input"))
    )
    (net (code "69") (name "Net-(LED33-DO)") (class "Default")
      (node (ref "LED33") (pin "1") (pinfunction "DO_1") (pintype "output"))
      (node (ref "LED34") (pin "6") (pinfunction "DI_6") (pintype "input"))
    )
    (net (code "70") (name "Net-(LED34-CKO)") (class "Default")
      (node (ref "LED34") (pin "2") (pinfunction "CKO_2") (pintype "output"))
      (node (ref "LED35") (pin "5") (pinfunction "CKI_5") (pintype "input"))
    )
    (net (code "71") (name "Net-(LED34-DO)") (class "Default")
      (node (ref "LED34") (pin "1") (pinfunction "DO_1") (pintype "output"))
      (node (ref "LED35") (pin "6") (pinfunction "DI_6") (pintype "input"))
    )
    (net (code "72") (name "Net-(LED35-CKO)") (class "Default")
      (node (ref "LED35") (pin "2") (pinfunction "CKO_2") (pintype "output"))
      (node (ref "LED36") (pin "5") (pinfunction "CKI_5") (pintype "input"))
    )
    (net (code "73") (name "Net-(LED35-DO)") (class "Default")
      (node (ref "LED35") (pin "1") (pinfunction "DO_1") (pintype "output"))
      (node (ref "LED36") (pin "6") (pinfunction "DI_6") (pintype "input"))
    )
    (net (code "74") (name "Net-(LED36-CKO)") (class "Default")
      (node (ref "LED36") (pin "2") (pinfunction "CKO_2") (pintype "output"))
      (node (ref "LED37") (pin "5") (pinfunction "CKI_5") (pintype "input"))
    )
    (net (code "75") (name "Net-(LED36-DO)") (class "Default")
      (node (ref "LED36") (pin "1") (pinfunction "DO_1") (pintype "output"))
      (node (ref "LED37") (pin "6") (pinfunction "DI_6") (pintype "input"))
    )
    (net (code "76") (name "Net-(LED37-CKO)") (class "Default")
      (node (ref "LED37") (pin "2") (pinfunction "CKO_2") (pintype "output"))
      (node (ref "LED38") (pin "5") (pinfunction "CKI_5") (pintype "input"))
    )
    (net (code "77") (name "Net-(LED37-DO)") (class "Default")
      (node (ref "LED37") (pin "1") (pinfunction "DO_1") (pintype "output"))
      (node (ref "LED38") (pin "6") (pinfunction "DI_6") (pintype "input"))
    )
    (net (code "78") (name "Net-(LED38-CKO)") (class "Default")
      (node (ref "LED38") (pin "2") (pinfunction "CKO_2") (pintype "output"))
      (node (ref "LED39") (pin "5") (pinfunction "CKI_5") (pintype "input"))
    )
    (net (code "79") (name "Net-(LED38-DO)") (class "Default")
      (node (ref "LED38") (pin "1") (pinfunction "DO_1") (pintype "output"))
      (node (ref "LED39") (pin "6") (pinfunction "DI_6") (pintype "input"))
    )
    (net (code "80") (name "Net-(LED39-CKO)") (class "Default")
      (node (ref "LED39") (pin "2") (pinfunction "CKO_2") (pintype "output"))
      (node (ref "LED40") (pin "5") (pinfunction "CKI_5") (pintype "input"))
    )
    (net (code "81") (name "Net-(LED39-DO)") (class "Default")
      (node (ref "LED39") (pin "1") (pinfunction "DO_1") (pintype "output"))
      (node (ref "LED40") (pin "6") (pinfunction "DI_6") (pintype "input"))
    )
    (net (code "82") (name "Net-(LED40-CKO)") (class "Default")
      (node (ref "LED40") (pin "2") (pinfunction "CKO_2") (pintype "output"))
      (node (ref "LED41") (pin "5") (pinfunction "CKI_5") (pintype "input"))
    )
    (net (code "83") (name "Net-(LED40-DO)") (class "Default")
      (node (ref "LED40") (pin "1") (pinfunction "DO_1") (pintype "output"))
      (node (ref "LED41") (pin "6") (pinfunction "DI_6") (pintype "input"))
    )
    (net (code "84") (name "Net-(LED41-CKO)") (class "Default")
      (node (ref "LED41") (pin "2") (pinfunction "CKO_2") (pintype "output"))
      (node (ref "LED42") (pin "5") (pinfunction "CKI_5") (pintype "input"))
    )
    (net (code "85") (name "Net-(LED41-DO)") (class "Default")
      (node (ref "LED41") (pin "1") (pinfunction "DO_1") (pintype "output"))
      (node (ref "LED42") (pin "6") (pinfunction "DI_6") (pintype "input"))
    )
    (net (code "86") (name "Net-(LED42-CKO)") (class "Default")
      (node (ref "LED42") (pin "2") (pinfunction "CKO_2") (pintype "output"))
      (node (ref "LED43") (pin "5") (pinfunction "CKI_5") (pintype "input"))
    )
    (net (code "87") (name "Net-(LED42-DO)") (class "Default")
      (node (ref "LED42") (pin "1") (pinfunction "DO_1") (pintype "output"))
      (node (ref "LED43") (pin "6") (pinfunction "DI_6") (pintype "input"))
    )
    (net (code "88") (name "Net-(LED43-CKO)") (class "Default")
      (node (ref "LED43") (pin "2") (pinfunction "CKO_2") (pintype "output"))
      (node (ref "LED44") (pin "5") (pinfunction "CKI_5") (pintype "input"))
    )
    (net (code "89") (name "Net-(LED43-DO)") (class "Default")
      (node (ref "LED43") (pin "1") (pinfunction "DO_1") (pintype "output"))
      (node (ref "LED44") (pin "6") (pinfunction "DI_6") (pintype "input"))
    )
    (net (code "90") (name "Net-(LED44-CKO)") (class "Default")
      (node (ref "LED44") (pin "2") (pinfunction "CKO_2") (pintype "output"))
      (node (ref "LED45") (pin "5") (pinfunction "CKI_5") (pintype "input"))
    )
    (net (code "91") (name "Net-(LED44-DO)") (class "Default")
      (node (ref "LED44") (pin "1") (pinfunction "DO_1") (pintype "output"))
      (node (ref "LED45") (pin "6") (pinfunction "DI_6") (pintype "input"))
    )
    (net (code "92") (name "Net-(LED45-CKO)") (class "Default")
      (node (ref "LED45") (pin "2") (pinfunction "CKO_2") (pintype "output"))
      (node (ref "LED46") (pin "5") (pinfunction "CKI_5") (pintype "input"))
    )
    (net (code "93") (name "Net-(LED45-DO)") (class "Default")
      (node (ref "LED45") (pin "1") (pinfunction "DO_1") (pintype "output"))
      (node (ref "LED46") (pin "6") (pinfunction "DI_6") (pintype "input"))
    )
    (net (code "94") (name "Net-(LED46-CKO)") (class "Default")
      (node (ref "LED46") (pin "2") (pinfunction "CKO_2") (pintype "output"))
      (node (ref "LED47") (pin "5") (pinfunction "CKI_5") (pintype "input"))
    )
    (net (code "95") (name "Net-(LED46-DO)") (class "Default")
      (node (ref "LED46") (pin "1") (pinfunction "DO_1") (pintype "output"))
      (node (ref "LED47") (pin "6") (pinfunction "DI_6") (pintype "input"))
    )
    (net (code "96") (name "Net-(LED47-CKO)") (class "Default")
      (node (ref "LED47") (pin "2") (pinfunction "CKO_2") (pintype "output"))
      (node (ref "LED48") (pin "5") (pinfunction "CKI_5") (pintype "input"))
    )
    (net (code "97") (name "Net-(LED47-DO)") (class "Default")
      (node (ref "LED47") (pin "1") (pinfunction "DO_1") (pintype "output"))
      (node (ref "LED48") (pin "6") (pinfunction "DI_6") (pintype "input"))
    )
    (net (code "98") (name "Net-(LED48-CKO)") (class "Default")
      (node (ref "LED48") (pin "2") (pinfunction "CKO_2") (pintype "output"))
      (node (ref "LED49") (pin "5") (pinfunction "CKI_5") (pintype "input"))
    )
    (net (code "99") (name "Net-(LED48-DO)") (class "Default")
      (node (ref "LED48") (pin "1") (pinfunction "DO_1") (pintype "output"))
      (node (ref "LED49") (pin "6") (pinfunction "DI_6") (pintype "input"))
    )
    (net (code "100") (name "Net-(LED49-CKO)") (class "Default")
      (node (ref "LED49") (pin "2") (pinfunction "CKO_2") (pintype "output"))
      (node (ref "LED50") (pin "5") (pinfunction "CKI_5") (pintype "input"))
    )
    (net (code "101") (name "Net-(LED49-DO)") (class "Default")
      (node (ref "LED49") (pin "1") (pinfunction "DO_1") (pintype "output"))
      (node (ref "LED50") (pin "6") (pinfunction "DI_6") (pintype "input"))
    )
    (net (code "102") (name "Net-(LED50-CKO)") (class "Default")
      (node (ref "LED50") (pin "2") (pinfunction "CKO_2") (pintype "output"))
      (node (ref "LED51") (pin "5") (pinfunction "CKI_5") (pintype "input"))
    )
    (net (code "103") (name "Net-(LED50-DO)") (class "Default")
      (node (ref "LED50") (pin "1") (pinfunction "DO_1") (pintype "output"))
      (node (ref "LED51") (pin "6") (pinfunction "DI_6") (pintype "input"))
    )
    (net (code "104") (name "Net-(LED51-CKO)") (class "Default")
      (node (ref "LED51") (pin "2") (pinfunction "CKO_2") (pintype "output"))
      (node (ref "LED52") (pin "5") (pinfunction "CKI_5") (pintype "input"))
    )
    (net (code "105") (name "Net-(LED51-DO)") (class "Default")
      (node (ref "LED51") (pin "1") (pinfunction "DO_1") (pintype "output"))
      (node (ref "LED52") (pin "6") (pinfunction "DI_6") (pintype "input"))
    )
    (net (code "106") (name "Net-(LED52-CKO)") (class "Default")
      (node (ref "LED52") (pin "2") (pinfunction "CKO_2") (pintype "output"))
      (node (ref "LED53") (pin "5") (pinfunction "CKI_5") (pintype "input"))
    )
    (net (code "107") (name "Net-(LED52-DO)") (class "Default")
      (node (ref "LED52") (pin "1") (pinfunction "DO_1") (pintype "output"))
      (node (ref "LED53") (pin "6") (pinfunction "DI_6") (pintype "input"))
    )
    (net (code "108") (name "Net-(LED53-CKO)") (class "Default")
      (node (ref "LED53") (pin "2") (pinfunction "CKO_2") (pintype "output"))
      (node (ref "LED54") (pin "5") (pinfunction "CKI_5") (pintype "input"))
    )
    (net (code "109") (name "Net-(LED53-DO)") (class "Default")
      (node (ref "LED53") (pin "1") (pinfunction "DO_1") (pintype "output"))
      (node (ref "LED54") (pin "6") (pinfunction "DI_6") (pintype "input"))
    )
    (net (code "110") (name "Net-(LED54-CKO)") (class "Default")
      (node (ref "LED54") (pin "2") (pinfunction "CKO_2") (pintype "output"))
      (node (ref "LED55") (pin "5") (pinfunction "CKI_5") (pintype "input"))
    )
    (net (code "111") (name "Net-(LED54-DO)") (class "Default")
      (node (ref "LED54") (pin "1") (pinfunction "DO_1") (pintype "output"))
      (node (ref "LED55") (pin "6") (pinfunction "DI_6") (pintype "input"))
    )
    (net (code "112") (name "Net-(LED55-CKO)") (class "Default")
      (node (ref "LED55") (pin "2") (pinfunction "CKO_2") (pintype "output"))
      (node (ref "LED56") (pin "5") (pinfunction "CKI_5") (pintype "input"))
    )
    (net (code "113") (name "Net-(LED55-DO)") (class "Default")
      (node (ref "LED55") (pin "1") (pinfunction "DO_1") (pintype "output"))
      (node (ref "LED56") (pin "6") (pinfunction "DI_6") (pintype "input"))
    )
    (net (code "114") (name "Net-(LED56-CKO)") (class "Default")
      (node (ref "LED56") (pin "2") (pinfunction "CKO_2") (pintype "output"))
      (node (ref "LED57") (pin "5") (pinfunction "CKI_5") (pintype "input"))
    )
    (net (code "115") (name "Net-(LED56-DO)") (class "Default")
      (node (ref "LED56") (pin "1") (pinfunction "DO_1") (pintype "output"))
      (node (ref "LED57") (pin "6") (pinfunction "DI_6") (pintype "input"))
    )
    (net (code "116") (name "Net-(LED57-CKO)") (class "Default")
      (node (ref "LED57") (pin "2") (pinfunction "CKO_2") (pintype "output"))
      (node (ref "LED58") (pin "5") (pinfunction "CKI_5") (pintype "input"))
    )
    (net (code "117") (name "Net-(LED57-DO)") (class "Default")
      (node (ref "LED57") (pin "1") (pinfunction "DO_1") (pintype "output"))
      (node (ref "LED58") (pin "6") (pinfunction "DI_6") (pintype "input"))
    )
    (net (code "118") (name "Net-(LED58-CKO)") (class "Default")
      (node (ref "LED58") (pin "2") (pinfunction "CKO_2") (pintype "output"))
      (node (ref "LED59") (pin "5") (pinfunction "CKI_5") (pintype "input"))
    )
    (net (code "119") (name "Net-(LED58-DO)") (class "Default")
      (node (ref "LED58") (pin "1") (pinfunction "DO_1") (pintype "output"))
      (node (ref "LED59") (pin "6") (pinfunction "DI_6") (pintype "input"))
    )
    (net (code "120") (name "Net-(LED59-CKO)") (class "Default")
      (node (ref "LED59") (pin "2") (pinfunction "CKO_2") (pintype "output"))
      (node (ref "LED60") (pin "5") (pinfunction "CKI_5") (pintype "input"))
    )
    (net (code "121") (name "Net-(LED59-DO)") (class "Default")
      (node (ref "LED59") (pin "1") (pinfunction "DO_1") (pintype "output"))
      (node (ref "LED60") (pin "6") (pinfunction "DI_6") (pintype "input"))
    )
    (net (code "122") (name "Net-(LED60-CKO)") (class "Default")
      (node (ref "LED60") (pin "2") (pinfunction "CKO_2") (pintype "output"))
      (node (ref "LED61") (pin "5") (pinfunction "CKI_5") (pintype "input"))
    )
    (net (code "123") (name "Net-(LED60-DO)") (class "Default")
      (node (ref "LED60") (pin "1") (pinfunction "DO_1") (pintype "output"))
      (node (ref "LED61") (pin "6") (pinfunction "DI_6") (pintype "input"))
    )
    (net (code "124") (name "Net-(LED61-CKO)") (class "Default")
      (node (ref "LED61") (pin "2") (pinfunction "CKO_2") (pintype "output"))
      (node (ref "LED62") (pin "5") (pinfunction "CKI_5") (pintype "input"))
    )
    (net (code "125") (name "Net-(LED61-DO)") (class "Default")
      (node (ref "LED61") (pin "1") (pinfunction "DO_1") (pintype "output"))
      (node (ref "LED62") (pin "6") (pinfunction "DI_6") (pintype "input"))
    )
    (net (code "126") (name "Net-(LED62-CKO)") (class "Default")
      (node (ref "LED62") (pin "2") (pinfunction "CKO_2") (pintype "output"))
      (node (ref "LED63") (pin "5") (pinfunction "CKI_5") (pintype "input"))
    )
    (net (code "127") (name "Net-(LED62-DO)") (class "Default")
      (node (ref "LED62") (pin "1") (pinfunction "DO_1") (pintype "output"))
      (node (ref "LED63") (pin "6") (pinfunction "DI_6") (pintype "input"))
    )
    (net (code "128") (name "Net-(LED63-CKO)") (class "Default")
      (node (ref "LED63") (pin "2") (pinfunction "CKO_2") (pintype "output"))
      (node (ref "LED64") (pin "5") (pinfunction "CKI_5") (pintype "input"))
    )
    (net (code "129") (name "Net-(LED63-DO)") (class "Default")
      (node (ref "LED63") (pin "1") (pinfunction "DO_1") (pintype "output"))
      (node (ref "LED64") (pin "6") (pinfunction "DI_6") (pintype "input"))
    )
    (net (code "130") (name "Net-(LED64-CKO)") (class "Default")
      (node (ref "CO") (pin "TP") (pinfunction "TP_TP") (pintype "input"))
      (node (ref "LED64") (pin "2") (pinfunction "CKO_2") (pintype "output"))
    )
    (net (code "131") (name "Net-(LED64-DO)") (class "Default")
      (node (ref "DO") (pin "TP") (pinfunction "TP_TP") (pintype "input"))
      (node (ref "LED64") (pin "1") (pinfunction "DO_1") (pintype "output"))
    )
    (net (code "132") (name "VDD") (class "Default")
      (node (ref "LED1") (pin "3") (pinfunction "VDD_3") (pintype "power_in"))
      (node (ref "LED10") (pin "3") (pinfunction "VDD_3") (pintype "power_in"))
      (node (ref "LED11") (pin "3") (pinfunction "VDD_3") (pintype "power_in"))
      (node (ref "LED12") (pin "3") (pinfunction "VDD_3") (pintype "power_in"))
      (node (ref "LED13") (pin "3") (pinfunction "VDD_3") (pintype "power_in"))
      (node (ref "LED14") (pin "3") (pinfunction "VDD_3") (pintype "power_in"))
      (node (ref "LED15") (pin "3") (pinfunction "VDD_3") (pintype "power_in"))
      (node (ref "LED16") (pin "3") (pinfunction "VDD_3") (pintype "power_in"))
      (node (ref "LED17") (pin "3") (pinfunction "VDD_3") (pintype "power_in"))
      (node (ref "LED18") (pin "3") (pinfunction "VDD_3") (pintype "power_in"))
      (node (ref "LED19") (pin "3") (pinfunction "VDD_3") (pintype "power_in"))
      (node (ref "LED2") (pin "3") (pinfunction "VDD_3") (pintype "power_in"))
      (node (ref "LED20") (pin "3") (pinfunction "VDD_3") (pintype "power_in"))
      (node (ref "LED21") (pin "3") (pinfunction "VDD_3") (pintype "power_in"))
      (node (ref "LED22") (pin "3") (pinfunction "VDD_3") (pintype "power_in"))
      (node (ref "LED23") (pin "3") (pinfunction "VDD_3") (pintype "power_in"))
      (node (ref "LED24") (pin "3") (pinfunction "VDD_3") (pintype "power_in"))
      (node (ref "LED25") (pin "3") (pinfunction "VDD_3") (pintype "power_in"))
      (node (ref "LED26") (pin "3") (pinfunction "VDD_3") (pintype "power_in"))
      (node (ref "LED27") (pin "3") (pinfunction "VDD_3") (pintype "power_in"))
      (node (ref "LED28") (pin "3") (pinfunction "VDD_3") (pintype "power_in"))
      (node (ref "LED29") (pin "3") (pinfunction "VDD_3") (pintype "power_in"))
      (node (ref "LED3") (pin "3") (pinfunction "VDD_3") (pintype "power_in"))
      (node (ref "LED30") (pin "3") (pinfunction "VDD_3") (pintype "power_in"))
      (node (ref "LED31") (pin "3") (pinfunction "VDD_3") (pintype "power_in"))
      (node (ref "LED32") (pin "3") (pinfunction "VDD_3") (pintype "power_in"))
      (node (ref "LED33") (pin "3") (pinfunction "VDD_3") (pintype "power_in"))
      (node (ref "LED34") (pin "3") (pinfunction "VDD_3") (pintype "power_in"))
      (node (ref "LED35") (pin "3") (pinfunction "VDD_3") (pintype "power_in"))
      (node (ref "LED36") (pin "3") (pinfunction "VDD_3") (pintype "power_in"))
      (node (ref "LED37") (pin "3") (pinfunction "VDD_3") (pintype "power_in"))
      (node (ref "LED38") (pin "3") (pinfunction "VDD_3") (pintype "power_in"))
      (node (ref "LED39") (pin "3") (pinfunction "VDD_3") (pintype "power_in"))
      (node (ref "LED4") (pin "3") (pinfunction "VDD_3") (pintype "power_in"))
      (node (ref "LED40") (pin "3") (pinfunction "VDD_3") (pintype "power_in"))
      (node (ref "LED41") (pin "3") (pinfunction "VDD_3") (pintype "power_in"))
      (node (ref "LED42") (pin "3") (pinfunction "VDD_3") (pintype "power_in"))
      (node (ref "LED43") (pin "3") (pinfunction "VDD_3") (pintype "power_in"))
      (node (ref "LED44") (pin "3") (pinfunction "VDD_3") (pintype "power_in"))
      (node (ref "LED45") (pin "3") (pinfunction "VDD_3") (pintype "power_in"))
      (node (ref "LED46") (pin "3") (pinfunction "VDD_3") (pintype "power_in"))
      (node (ref "LED47") (pin "3") (pinfunction "VDD_3") (pintype "power_in"))
      (node (ref "LED48") (pin "3") (pinfunction "VDD_3") (pintype "power_in"))
      (node (ref "LED49") (pin "3") (pinfunction "VDD_3") (pintype "power_in"))
      (node (ref "LED5") (pin "3") (pinfunction "VDD_3") (pintype "power_in"))
      (node (ref "LED50") (pin "3") (pinfunction "VDD_3") (pintype "power_in"))
      (node (ref "LED51") (pin "3") (pinfunction "VDD_3") (pintype "power_in"))
      (node (ref "LED52") (pin "3") (pinfunction "VDD_3") (pintype "power_in"))
      (node (ref "LED53") (pin "3") (pinfunction "VDD_3") (pintype "power_in"))
      (node (ref "LED54") (pin "3") (pinfunction "VDD_3") (pintype "power_in"))
      (node (ref "LED55") (pin "3") (pinfunction "VDD_3") (pintype "power_in"))
      (node (ref "LED56") (pin "3") (pinfunction "VDD_3") (pintype "power_in"))
      (node (ref "LED57") (pin "3") (pinfunction "VDD_3") (pintype "power_in"))
      (node (ref "LED58") (pin "3") (pinfunction "VDD_3") (pintype "power_in"))
      (node (ref "LED59") (pin "3") (pinfunction "VDD_3") (pintype "power_in"))
      (node (ref "LED6") (pin "3") (pinfunction "VDD_3") (pintype "power_in"))
      (node (ref "LED60") (pin "3") (pinfunction "VDD_3") (pintype "power_in"))
      (node (ref "LED61") (pin "3") (pinfunction "VDD_3") (pintype "power_in"))
      (node (ref "LED62") (pin "3") (pinfunction "VDD_3") (pintype "power_in"))
      (node (ref "LED63") (pin "3") (pinfunction "VDD_3") (pintype "power_in"))
      (node (ref "LED64") (pin "3") (pinfunction "VDD_3") (pintype "power_in"))
      (node (ref "LED7") (pin "3") (pinfunction "VDD_3") (pintype "power_in"))
      (node (ref "LED8") (pin "3") (pinfunction "VDD_3") (pintype "power_in"))
      (node (ref "LED9") (pin "3") (pinfunction "VDD_3") (pintype "power_in"))
      (node (ref "V1") (pin "TP") (pinfunction "TP_TP") (pintype "input"))
      (node (ref "V2") (pin "TP") (pinfunction "TP_TP") (pintype "input"))
      (node (ref "V3") (pin "TP") (pinfunction "TP_TP") (pintype "input"))
    )
  )
)
